# main.net
KiCad netlist of a schematic drawn in Altium Designer
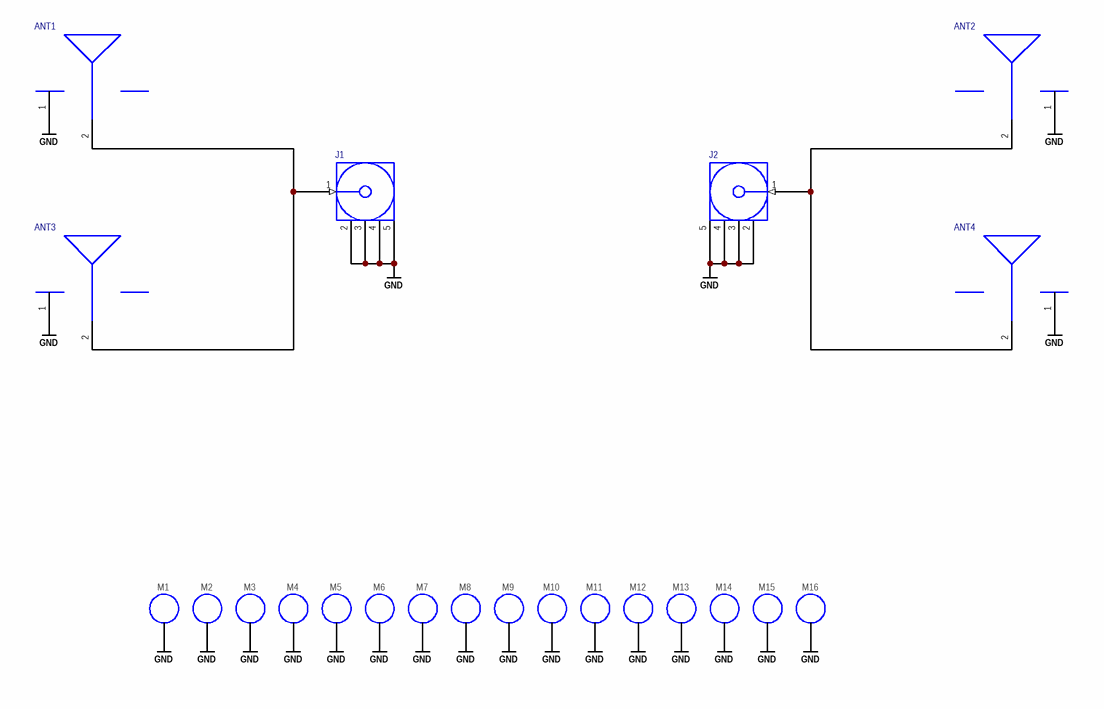
[diagram p0: main.SchDoc]

(export (version "E")
  (design (tool "Eeschema 10.0.6"))
  (components
    (comp (ref "ANT1")
      (value "antenna_plane")
      (footprint "antenna_plane")
      (fields (field (name "MANUFACTURER") "Siglabs"))
      (libsource (lib "higgsant") (part "antenna_plane"))
    )
    (comp (ref "ANT2")
      (value "antenna_plane")
      (footprint "antenna_plane")
      (fields (field (name "MANUFACTURER") "Siglabs"))
      (libsource (lib "higgsant") (part "antenna_plane"))
    )
    (comp (ref "ANT3")
      (value "antenna_plane")
      (footprint "antenna_plane")
      (fields (field (name "MANUFACTURER") "Siglabs"))
      (libsource (lib "higgsant") (part "antenna_plane"))
    )
    (comp (ref "ANT4")
      (value "antenna_plane")
      (footprint "antenna_plane")
      (fields (field (name "MANUFACTURER") "Siglabs"))
      (libsource (lib "higgsant") (part "antenna_plane"))
    )
    (comp (ref "J1")
      (value "142146")
      (footprint "amphenol:142146")
      (description "Connector; RF Coaxial, SMB, Thru-Hole; 5 Position; Right-Angle")
      (fields (field (name "MANUFACTURER") "Amphenol RF"))
      (libsource (lib "Miscellaneous Connectors") (part "COAX-F"))
    )
    (comp (ref "J2")
      (value "142146")
      (footprint "amphenol:142146")
      (description "Connector; RF Coaxial, SMB, Thru-Hole; 5 Position; Right-Angle")
      (fields (field (name "MANUFACTURER") "Amphenol RF"))
      (libsource (lib "Miscellaneous Connectors") (part "COAX-F"))
    )
    (comp (ref "M1")
      (value "MOUNT")
      (footprint "MOUNTM3")
      (description "M3 Standard Fit Hole")
      (libsource (lib "copper_suicide") (part "MOUNT"))
    )
    (comp (ref "M2")
      (value "MOUNT")
      (footprint "MOUNTM3")
      (description "M3 Standard Fit Hole")
      (libsource (lib "copper_suicide") (part "MOUNT"))
    )
    (comp (ref "M3")
      (value "MOUNT")
      (footprint "MOUNTM3")
      (description "M3 Standard Fit Hole")
      (libsource (lib "copper_suicide") (part "MOUNT"))
    )
    (comp (ref "M4")
      (value "MOUNT")
      (footprint "MOUNTM3")
      (description "M3 Standard Fit Hole")
      (libsource (lib "copper_suicide") (part "MOUNT"))
    )
    (comp (ref "M5")
      (value "MOUNT")
      (footprint "MOUNTM3")
      (description "M3 Standard Fit Hole")
      (libsource (lib "copper_suicide") (part "MOUNT"))
    )
    (comp (ref "M6")
      (value "MOUNT")
      (footprint "MOUNTM3")
      (description "M3 Standard Fit Hole")
      (libsource (lib "copper_suicide") (part "MOUNT"))
    )
    (comp (ref "M7")
      (value "MOUNT")
      (footprint "MOUNTM3")
      (description "M3 Standard Fit Hole")
      (libsource (lib "copper_suicide") (part "MOUNT"))
    )
    (comp (ref "M8")
      (value "MOUNT")
      (footprint "MOUNTM3")
      (description "M3 Standard Fit Hole")
      (libsource (lib "copper_suicide") (part "MOUNT"))
    )
    (comp (ref "M9")
      (value "MOUNT")
      (footprint "MOUNTM3")
      (description "M3 Standard Fit Hole")
      (libsource (lib "copper_suicide") (part "MOUNT"))
    )
    (comp (ref "M10")
      (value "MOUNT")
      (footprint "MOUNTM3")
      (description "M3 Standard Fit Hole")
      (libsource (lib "copper_suicide") (part "MOUNT"))
    )
    (comp (ref "M11")
      (value "MOUNT")
      (footprint "MOUNTM3")
      (description "M3 Standard Fit Hole")
      (libsource (lib "copper_suicide") (part "MOUNT"))
    )
    (comp (ref "M12")
      (value "MOUNT")
      (footprint "MOUNTM3")
      (description "M3 Standard Fit Hole")
      (libsource (lib "copper_suicide") (part "MOUNT"))
    )
    (comp (ref "M13")
      (value "MOUNT")
      (footprint "MOUNTM3")
      (description "M3 Standard Fit Hole")
      (libsource (lib "copper_suicide") (part "MOUNT"))
    )
    (comp (ref "M14")
      (value "MOUNT")
      (footprint "MOUNTM3")
      (description "M3 Standard Fit Hole")
      (libsource (lib "copper_suicide") (part "MOUNT"))
    )
    (comp (ref "M15")
      (value "MOUNT")
      (footprint "MOUNTM3")
      (description "M3 Standard Fit Hole")
      (libsource (lib "copper_suicide") (part "MOUNT"))
    )
    (comp (ref "M16")
      (value "MOUNT")
      (footprint "MOUNTM3")
      (description "M3 Standard Fit Hole")
      (libsource (lib "copper_suicide") (part "MOUNT"))
    )
  )
  (nets
    (net (code "1") (name "GND") (class "Default")
      (node (ref "ANT1") (pin "1") (pinfunction "1_1") (pintype "passive"))
      (node (ref "ANT2") (pin "1") (pinfunction "1_1") (pintype "passive"))
      (node (ref "ANT3") (pin "1") (pinfunction "1_1") (pintype "passive"))
      (node (ref "ANT4") (pin "1") (pinfunction "1_1") (pintype "passive"))
      (node (ref "J1") (pin "2") (pinfunction "GND_2") (pintype "power_in"))
      (node (ref "J1") (pin "3") (pinfunction "GND_3") (pintype "power_in"))
      (node (ref "J1") (pin "4") (pinfunction "GND_4") (pintype "power_in"))
      (node (ref "J1") (pin "5") (pinfunction "GND_5") (pintype "power_in"))
      (node (ref "J2") (pin "2") (pinfunction "GND_2") (pintype "power_in"))
      (node (ref "J2") (pin "3") (pinfunction "GND_3") (pintype "power_in"))
      (node (ref "J2") (pin "4") (pinfunction "GND_4") (pintype "power_in"))
      (node (ref "J2") (pin "5") (pinfunction "GND_5") (pintype "power_in"))
      (node (ref "M1") (pin "1") (pinfunction "MNT_1") (pintype "passive"))
      (node (ref "M10") (pin "1") (pinfunction "MNT_1") (pintype "passive"))
      (node (ref "M11") (pin "1") (pinfunction "MNT_1") (pintype "passive"))
      (node (ref "M12") (pin "1") (pinfunction "MNT_1") (pintype "passive"))
      (node (ref "M13") (pin "1") (pinfunction "MNT_1") (pintype "passive"))
      (node (ref "M14") (pin "1") (pinfunction "MNT_1") (pintype "passive"))
      (node (ref "M15") (pin "1") (pinfunction "MNT_1") (pintype "passive"))
      (node (ref "M16") (pin "1") (pinfunction "MNT_1") (pintype "passive"))
      (node (ref "M2") (pin "1") (pinfunction "MNT_1") (pintype "passive"))
      (node (ref "M3") (pin "1") (pinfunction "MNT_1") (pintype "passive"))
      (node (ref "M4") (pin "1") (pinfunction "MNT_1") (pintype "passive"))
      (node (ref "M5") (pin "1") (pinfunction "MNT_1") (pintype "passive"))
      (node (ref "M6") (pin "1") (pinfunction "MNT_1") (pintype "passive"))
      (node (ref "M7") (pin "1") (pinfunction "MNT_1") (pintype "passive"))
      (node (ref "M8") (pin "1") (pinfunction "MNT_1") (pintype "passive"))
      (node (ref "M9") (pin "1") (pinfunction "MNT_1") (pintype "passive"))
    )
    (net (code "2") (name "Net-(J1-Signal)") (class "Default")
      (node (ref "ANT1") (pin "2") (pinfunction "2_2") (pintype "passive"))
      (node (ref "ANT3") (pin "2") (pinfunction "2_2") (pintype "passive"))
      (node (ref "J1") (pin "1") (pinfunction "Signal_1") (pintype "input"))
    )
    (net (code "3") (name "Net-(J2-Signal)") (class "Default")
      (node (ref "ANT2") (pin "2") (pinfunction "2_2") (pintype "passive"))
      (node (ref "ANT4") (pin "2") (pinfunction "2_2") (pintype "passive"))
      (node (ref "J2") (pin "1") (pinfunction "Signal_1") (pintype "input"))
    )
  )
)
